# H-Bridge_schematic.net
KiCad netlist of a schematic drawn in Altium Designer
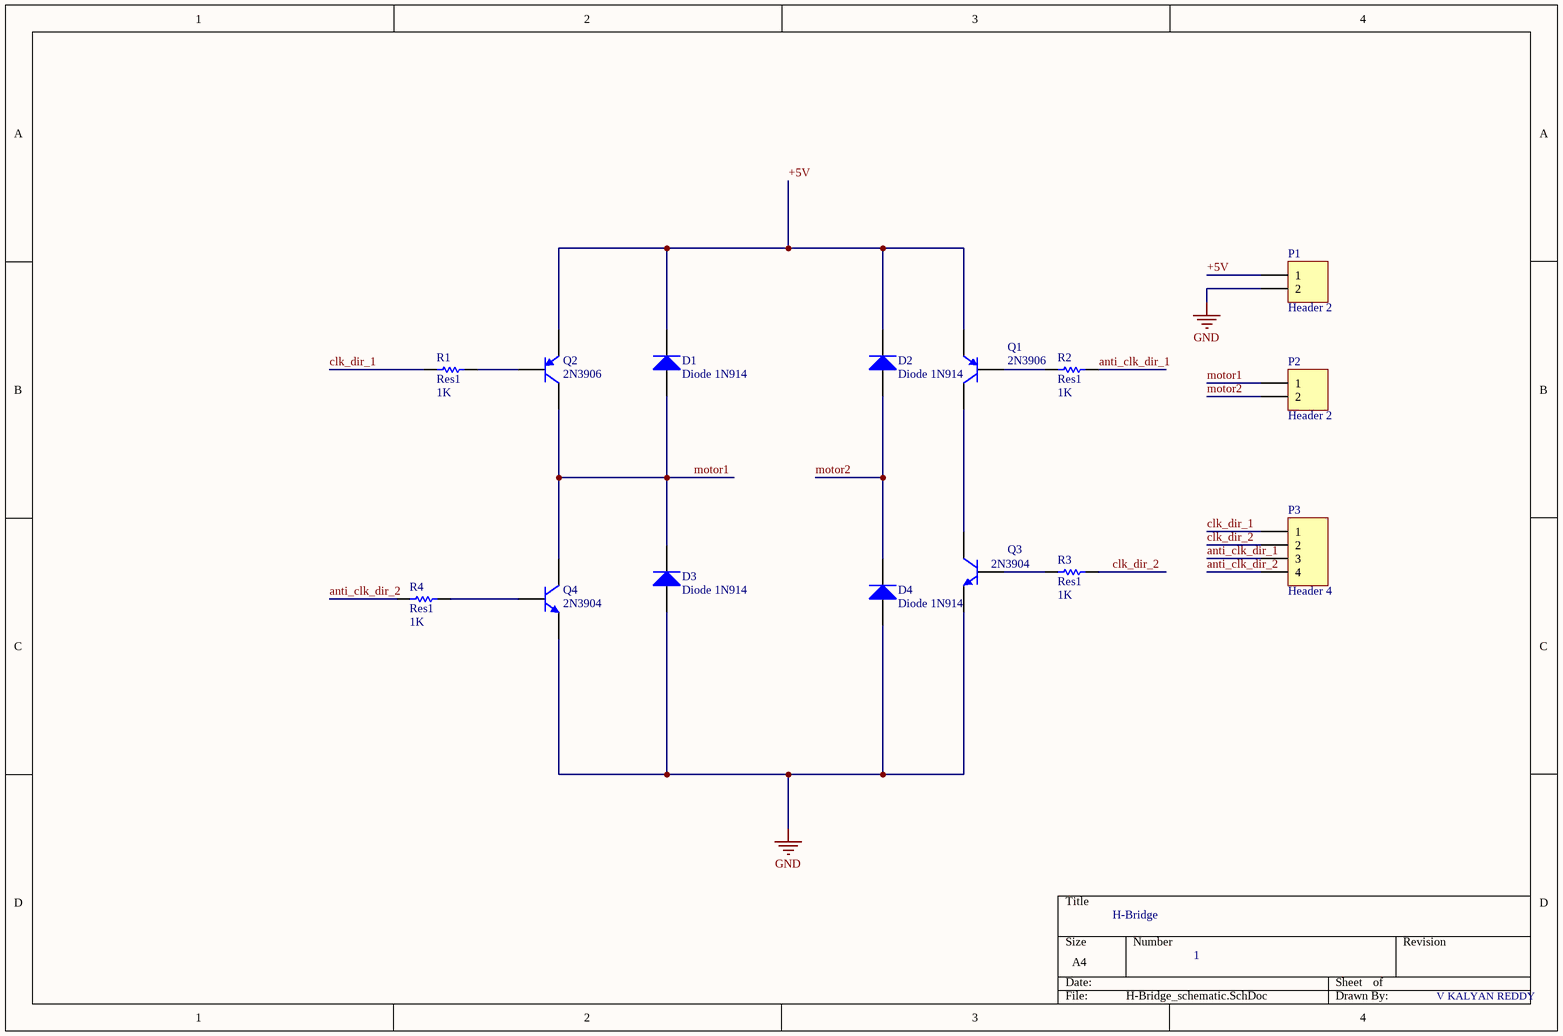
[diagram p0: H-Bridge_schematic.SchDoc]

(export (version "E")
  (design (tool "Eeschema 10.0.6"))
  (components
    (comp (ref "D1")
      (value "Diode 1N914")
      (footprint "DO-35")
      (description "High Conductance Fast Diode")
      (fields (field (name "PUBLISHER") "Altium Limited"))
      (libsource (lib "Miscellaneous Devices") (part "Diode 1N914"))
    )
    (comp (ref "D2")
      (value "Diode 1N914")
      (footprint "DO-35")
      (description "High Conductance Fast Diode")
      (fields (field (name "PUBLISHER") "Altium Limited"))
      (libsource (lib "Miscellaneous Devices") (part "Diode 1N914"))
    )
    (comp (ref "D3")
      (value "Diode 1N914")
      (footprint "DO-35")
      (description "High Conductance Fast Diode")
      (fields (field (name "PUBLISHER") "Altium Limited"))
      (libsource (lib "Miscellaneous Devices") (part "Diode 1N914"))
    )
    (comp (ref "D4")
      (value "Diode 1N914")
      (footprint "DO-35")
      (description "High Conductance Fast Diode")
      (fields (field (name "PUBLISHER") "Altium Limited"))
      (libsource (lib "Miscellaneous Devices") (part "Diode 1N914"))
    )
    (comp (ref "P1")
      (value "Header 2")
      (footprint "HDR1X2")
      (description "Header, 2-Pin")
      (fields (field (name "PUBLISHER") "Altium Limited"))
      (libsource (lib "Miscellaneous Connectors") (part "Header 2"))
    )
    (comp (ref "P2")
      (value "Header 2")
      (footprint "HDR1X2")
      (description "Header, 2-Pin")
      (fields (field (name "PUBLISHER") "Altium Limited"))
      (libsource (lib "Miscellaneous Connectors") (part "Header 2"))
    )
    (comp (ref "P3")
      (value "Header 4")
      (footprint "HDR1X4")
      (description "Header, 4-Pin")
      (fields (field (name "PUBLISHER") "Altium Limited"))
      (libsource (lib "Miscellaneous Connectors") (part "Header 4"))
    )
    (comp (ref "Q1")
      (value "2N3906")
      (footprint "TO-92A")
      (description "PNP General Purpose Amplifier")
      (fields (field (name "PUBLISHER") "Altium Limited"))
      (libsource (lib "Miscellaneous Devices") (part "2N3906"))
    )
    (comp (ref "Q2")
      (value "2N3906")
      (footprint "TO-92A")
      (description "PNP General Purpose Amplifier")
      (fields (field (name "PUBLISHER") "Altium Limited"))
      (libsource (lib "Miscellaneous Devices") (part "2N3906"))
    )
    (comp (ref "Q3")
      (value "2N3904")
      (footprint "TO-92A")
      (description "NPN General Purpose Amplifier")
      (fields (field (name "PUBLISHER") "Altium Limited"))
      (libsource (lib "Miscellaneous Devices") (part "2N3904"))
    )
    (comp (ref "Q4")
      (value "2N3904")
      (footprint "TO-92A")
      (description "NPN General Purpose Amplifier")
      (fields (field (name "PUBLISHER") "Altium Limited"))
      (libsource (lib "Miscellaneous Devices") (part "2N3904"))
    )
    (comp (ref "R1")
      (value "Res1")
      (footprint "AXIAL-0.3")
      (description "Resistor")
      (fields (field (name "ALTIUM_VALUE") "1K") (field (name "PUBLISHER") "Altium Limited"))
      (libsource (lib "Miscellaneous Devices") (part "Res1"))
    )
    (comp (ref "R2")
      (value "Res1")
      (footprint "AXIAL-0.3")
      (description "Resistor")
      (fields (field (name "ALTIUM_VALUE") "1K") (field (name "PUBLISHER") "Altium Limited"))
      (libsource (lib "Miscellaneous Devices") (part "Res1"))
    )
    (comp (ref "R3")
      (value "Res1")
      (footprint "AXIAL-0.3")
      (description "Resistor")
      (fields (field (name "ALTIUM_VALUE") "1K") (field (name "PUBLISHER") "Altium Limited"))
      (libsource (lib "Miscellaneous Devices") (part "Res1"))
    )
    (comp (ref "R4")
      (value "Res1")
      (footprint "AXIAL-0.3")
      (description "Resistor")
      (fields (field (name "ALTIUM_VALUE") "1K") (field (name "PUBLISHER") "Altium Limited"))
      (libsource (lib "Miscellaneous Devices") (part "Res1"))
    )
  )
  (nets
    (net (code "1") (name "/+5V") (class "Default")
      (node (ref "D1") (pin "2") (pinfunction "K_2") (pintype "passive"))
      (node (ref "D2") (pin "2") (pinfunction "K_2") (pintype "passive"))
      (node (ref "P1") (pin "1") (pinfunction "1_1") (pintype "passive"))
      (node (ref "Q1") (pin "1") (pinfunction "E_1") (pintype "passive"))
      (node (ref "Q2") (pin "1") (pinfunction "E_1") (pintype "passive"))
    )
    (net (code "2") (name "/anti_clk_dir_1") (class "Default")
      (node (ref "P3") (pin "3") (pinfunction "3_3") (pintype "passive"))
      (node (ref "R2") (pin "2") (pinfunction "2_2") (pintype "passive"))
    )
    (net (code "3") (name "/anti_clk_dir_2") (class "Default")
      (node (ref "P3") (pin "4") (pinfunction "4_4") (pintype "passive"))
      (node (ref "R4") (pin "1") (pinfunction "1_1") (pintype "passive"))
    )
    (net (code "4") (name "/clk_dir_1") (class "Default")
      (node (ref "P3") (pin "1") (pinfunction "1_1") (pintype "passive"))
      (node (ref "R1") (pin "1") (pinfunction "1_1") (pintype "passive"))
    )
    (net (code "5") (name "/clk_dir_2") (class "Default")
      (node (ref "P3") (pin "2") (pinfunction "2_2") (pintype "passive"))
      (node (ref "R3") (pin "2") (pinfunction "2_2") (pintype "passive"))
    )
    (net (code "6") (name "/motor1") (class "Default")
      (node (ref "D1") (pin "1") (pinfunction "A_1") (pintype "passive"))
      (node (ref "D3") (pin "2") (pinfunction "K_2") (pintype "passive"))
      (node (ref "P2") (pin "1") (pinfunction "1_1") (pintype "passive"))
      (node (ref "Q2") (pin "3") (pinfunction "C_3") (pintype "passive"))
      (node (ref "Q4") (pin "3") (pinfunction "C_3") (pintype "passive"))
    )
    (net (code "7") (name "/motor2") (class "Default")
      (node (ref "D2") (pin "1") (pinfunction "A_1") (pintype "passive"))
      (node (ref "D4") (pin "2") (pinfunction "K_2") (pintype "passive"))
      (node (ref "P2") (pin "2") (pinfunction "2_2") (pintype "passive"))
    )
    (net (code "8") (name "GND") (class "Default")
      (node (ref "D3") (pin "1") (pinfunction "A_1") (pintype "passive"))
      (node (ref "D4") (pin "1") (pinfunction "A_1") (pintype "passive"))
      (node (ref "P1") (pin "2") (pinfunction "2_2") (pintype "passive"))
      (node (ref "Q3") (pin "1") (pinfunction "E_1") (pintype "passive"))
      (node (ref "Q4") (pin "1") (pinfunction "E_1") (pintype "passive"))
    )
    (net (code "9") (name "Net-(Q1-B)") (class "Default")
      (node (ref "Q1") (pin "2") (pinfunction "B_2") (pintype "passive"))
      (node (ref "R2") (pin "1") (pinfunction "1_1") (pintype "passive"))
    )
    (net (code "10") (name "Net-(Q1-C)") (class "Default")
      (node (ref "Q1") (pin "3") (pinfunction "C_3") (pintype "passive"))
      (node (ref "Q3") (pin "3") (pinfunction "C_3") (pintype "passive"))
    )
    (net (code "11") (name "Net-(Q2-B)") (class "Default")
      (node (ref "Q2") (pin "2") (pinfunction "B_2") (pintype "passive"))
      (node (ref "R1") (pin "2") (pinfunction "2_2") (pintype "passive"))
    )
    (net (code "12") (name "Net-(Q3-B)") (class "Default")
      (node (ref "Q3") (pin "2") (pinfunction "B_2") (pintype "passive"))
      (node (ref "R3") (pin "1") (pinfunction "1_1") (pintype "passive"))
    )
    (net (code "13") (name "Net-(Q4-B)") (class "Default")
      (node (ref "Q4") (pin "2") (pinfunction "B_2") (pintype "passive"))
      (node (ref "R4") (pin "2") (pinfunction "2_2") (pintype "passive"))
    )
  )
)
